# SCH_New-Project_2025-04-22.net
KiCad netlist of a schematic drawn in EasyEDA
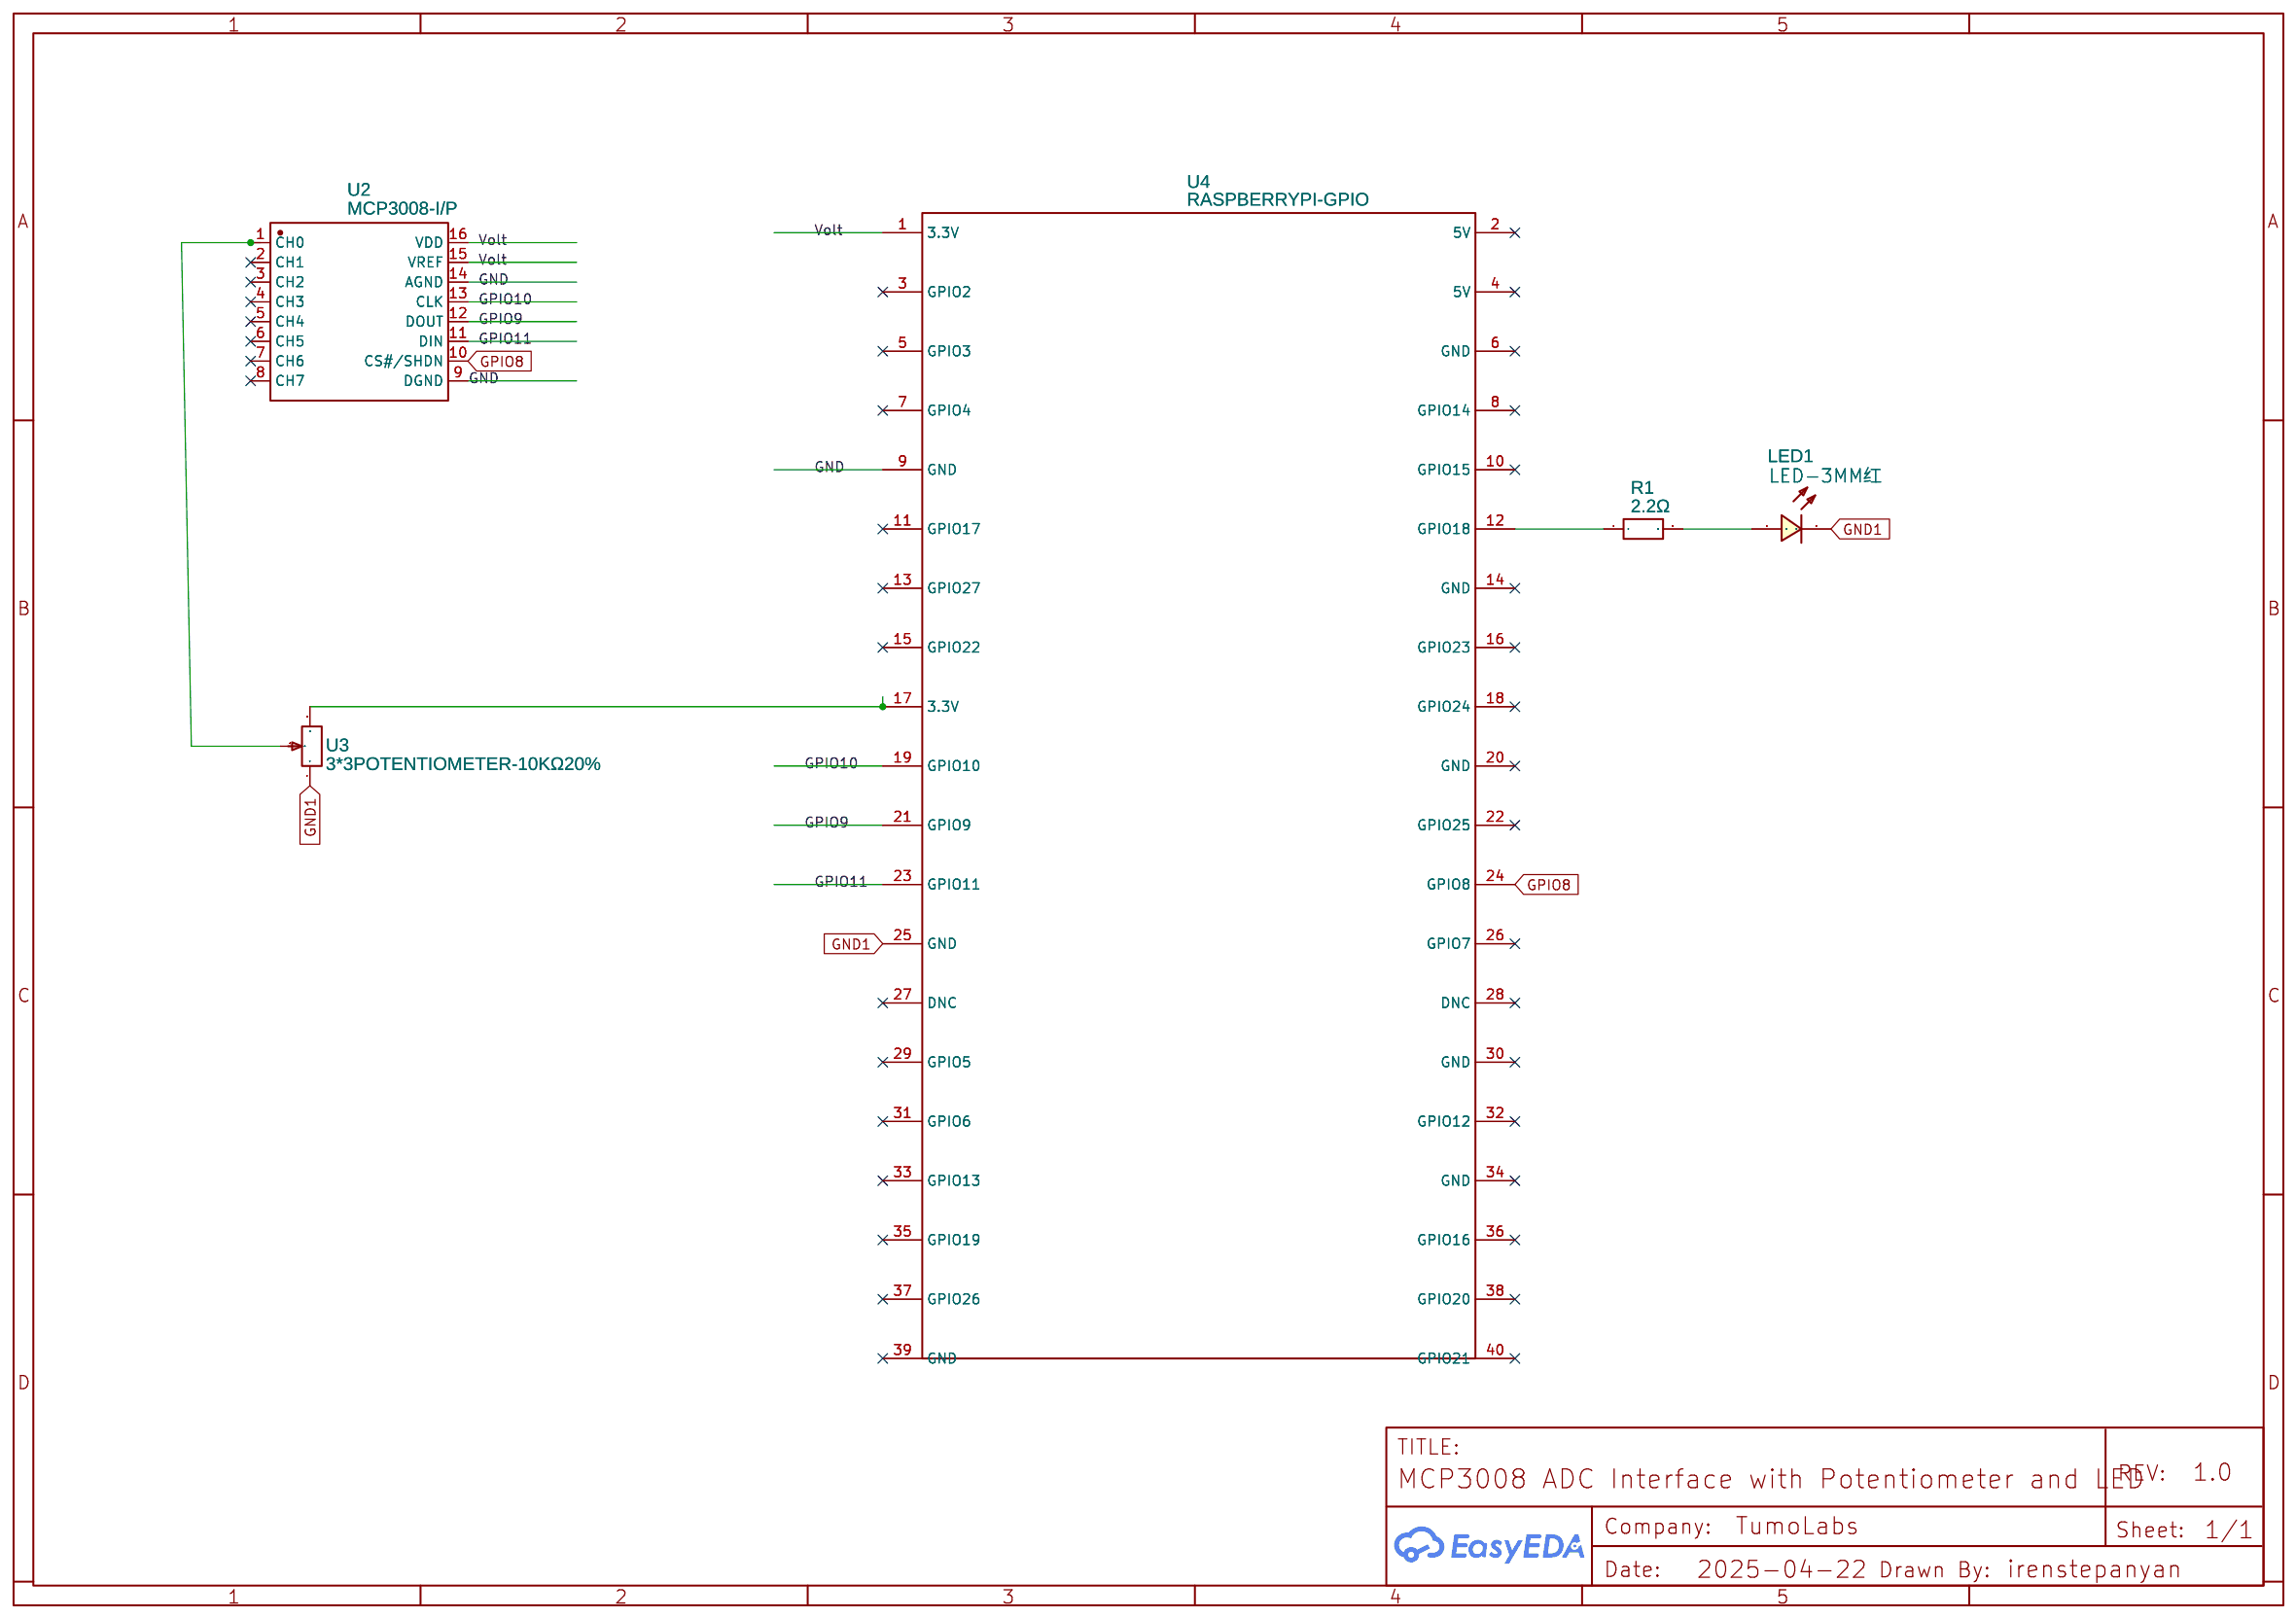
[diagram p0: schematic sheet]

(export (version "E")
  (design (tool "Eeschema 10.0.6"))
  (components
    (comp (ref "LED1")
      (value "LED-3MM红")
      (fields (field (name "Manufacturer Part") "LED-3mm红"))
      (libsource (lib "") (part "LED-3MM红"))
    )
    (comp (ref "R1")
      (value "2.2Ω")
      (fields
        (field (name "Manufacturer Part") "CERAMIC RESISTOR 10W/ 2,2 OHM")
        (field (name "Manufacturer") "Visaton")
      )
      (libsource (lib "") (part "CERAMIC RESISTOR 10W/ 2,2 OHM"))
    )
    (comp (ref "U2")
      (value "MCP3008-I/P")
      (fields (field (name "Manufacturer") "MICROCHIP(美国微芯)"))
      (libsource (lib "") (part "MCP3008-I/P"))
    )
    (comp (ref "U3")
      (value "3*3POTENTIOMETER-10KΩ20%")
      (fields (field (name "Manufacturer Part") "3*3Potentiometer-10kΩ20%"))
      (libsource (lib "") (part "3*3POTENTIOMETER-10KΩ20%"))
    )
    (comp (ref "U4") (value "RASPBERRYPI-GPIO") (libsource (lib "") (part "RASPBERRYPI-GPIO")))
  )
  (nets
    (net (code "1") (name "/GND") (class "Default")
      (node (ref "U2") (pin "14") (pinfunction "AGND_14") (pintype "unspecified"))
      (node (ref "U2") (pin "9") (pinfunction "DGND_9") (pintype "unspecified"))
      (node (ref "U4") (pin "9") (pinfunction "GND_9") (pintype "unspecified"))
    )
    (net (code "2") (name "/GPIO9") (class "Default")
      (node (ref "U2") (pin "12") (pinfunction "DOUT_12") (pintype "unspecified"))
      (node (ref "U4") (pin "21") (pinfunction "GPIO9_21") (pintype "unspecified"))
    )
    (net (code "3") (name "/GPIO10") (class "Default")
      (node (ref "U2") (pin "13") (pinfunction "CLK_13") (pintype "unspecified"))
      (node (ref "U4") (pin "19") (pinfunction "GPIO10_19") (pintype "unspecified"))
    )
    (net (code "4") (name "/GPIO11") (class "Default")
      (node (ref "U2") (pin "11") (pinfunction "DIN_11") (pintype "unspecified"))
      (node (ref "U4") (pin "23") (pinfunction "GPIO11_23") (pintype "unspecified"))
    )
    (net (code "5") (name "/Volt") (class "Default")
      (node (ref "U2") (pin "15") (pinfunction "VREF_15") (pintype "unspecified"))
      (node (ref "U2") (pin "16") (pinfunction "VDD_16") (pintype "unspecified"))
      (node (ref "U4") (pin "1") (pinfunction "3.3V_1") (pintype "unspecified"))
    )
    (net (code "6") (name "GND1") (class "Default")
      (node (ref "LED1") (pin "2") (pinfunction "2_2") (pintype "unspecified"))
      (node (ref "U3") (pin "1") (pinfunction "1_1") (pintype "input"))
      (node (ref "U4") (pin "25") (pinfunction "GND_25") (pintype "unspecified"))
    )
    (net (code "7") (name "GPIO8") (class "Default")
      (node (ref "U2") (pin "10") (pinfunction "CS#/SHDN_10") (pintype "unspecified"))
      (node (ref "U4") (pin "24") (pinfunction "GPIO8_24") (pintype "unspecified"))
    )
    (net (code "8") (name "Net-(LED1-Pad1)") (class "Default")
      (node (ref "LED1") (pin "1") (pinfunction "1_1") (pintype "unspecified"))
      (node (ref "R1") (pin "2") (pinfunction "2_2") (pintype "unspecified"))
    )
    (net (code "9") (name "Net-(U2-CH0)") (class "Default")
      (node (ref "U2") (pin "1") (pinfunction "CH0_1") (pintype "unspecified"))
      (node (ref "U3") (pin "2") (pinfunction "2_2") (pintype "input"))
    )
    (net (code "10") (name "Net-(U3-Pad3)") (class "Default")
      (node (ref "U3") (pin "3") (pinfunction "3_3") (pintype "input"))
      (node (ref "U4") (pin "17") (pinfunction "3.3V_17") (pintype "unspecified"))
    )
    (net (code "11") (name "Net-(U4-GPIO18)") (class "Default")
      (node (ref "R1") (pin "1") (pinfunction "1_1") (pintype "unspecified"))
      (node (ref "U4") (pin "12") (pinfunction "GPIO18_12") (pintype "unspecified"))
    )
    (net (code "12") (name "unconnected-(U2-CH1-Pad2)") (class "Default")
      (node (ref "U2") (pin "2") (pinfunction "CH1_2") (pintype "unspecified+no_connect"))
    )
    (net (code "13") (name "unconnected-(U2-CH2-Pad3)") (class "Default")
      (node (ref "U2") (pin "3") (pinfunction "CH2_3") (pintype "unspecified+no_connect"))
    )
    (net (code "14") (name "unconnected-(U2-CH3-Pad4)") (class "Default")
      (node (ref "U2") (pin "4") (pinfunction "CH3_4") (pintype "unspecified+no_connect"))
    )
    (net (code "15") (name "unconnected-(U2-CH4-Pad5)") (class "Default")
      (node (ref "U2") (pin "5") (pinfunction "CH4_5") (pintype "unspecified+no_connect"))
    )
    (net (code "16") (name "unconnected-(U2-CH5-Pad6)") (class "Default")
      (node (ref "U2") (pin "6") (pinfunction "CH5_6") (pintype "unspecified+no_connect"))
    )
    (net (code "17") (name "unconnected-(U2-CH6-Pad7)") (class "Default")
      (node (ref "U2") (pin "7") (pinfunction "CH6_7") (pintype "unspecified+no_connect"))
    )
    (net (code "18") (name "unconnected-(U2-CH7-Pad8)") (class "Default")
      (node (ref "U2") (pin "8") (pinfunction "CH7_8") (pintype "unspecified+no_connect"))
    )
    (net (code "19") (name "unconnected-(U4-5V-Pad2)") (class "Default")
      (node (ref "U4") (pin "2") (pinfunction "5V_2") (pintype "unspecified+no_connect"))
    )
    (net (code "20") (name "unconnected-(U4-5V-Pad4)") (class "Default")
      (node (ref "U4") (pin "4") (pinfunction "5V_4") (pintype "unspecified+no_connect"))
    )
    (net (code "21") (name "unconnected-(U4-DNC-Pad27)") (class "Default")
      (node (ref "U4") (pin "27") (pinfunction "DNC_27") (pintype "unspecified+no_connect"))
    )
    (net (code "22") (name "unconnected-(U4-DNC-Pad28)") (class "Default")
      (node (ref "U4") (pin "28") (pinfunction "DNC_28") (pintype "unspecified+no_connect"))
    )
    (net (code "23") (name "unconnected-(U4-GND-Pad6)") (class "Default")
      (node (ref "U4") (pin "6") (pinfunction "GND_6") (pintype "unspecified+no_connect"))
    )
    (net (code "24") (name "unconnected-(U4-GND-Pad14)") (class "Default")
      (node (ref "U4") (pin "14") (pinfunction "GND_14") (pintype "unspecified+no_connect"))
    )
    (net (code "25") (name "unconnected-(U4-GND-Pad20)") (class "Default")
      (node (ref "U4") (pin "20") (pinfunction "GND_20") (pintype "unspecified+no_connect"))
    )
    (net (code "26") (name "unconnected-(U4-GND-Pad30)") (class "Default")
      (node (ref "U4") (pin "30") (pinfunction "GND_30") (pintype "unspecified+no_connect"))
    )
    (net (code "27") (name "unconnected-(U4-GND-Pad34)") (class "Default")
      (node (ref "U4") (pin "34") (pinfunction "GND_34") (pintype "unspecified+no_connect"))
    )
    (net (code "28") (name "unconnected-(U4-GND-Pad39)") (class "Default")
      (node (ref "U4") (pin "39") (pinfunction "GND_39") (pintype "unspecified+no_connect"))
    )
    (net (code "29") (name "unconnected-(U4-GPIO2-Pad3)") (class "Default")
      (node (ref "U4") (pin "3") (pinfunction "GPIO2_3") (pintype "unspecified+no_connect"))
    )
    (net (code "30") (name "unconnected-(U4-GPIO3-Pad5)") (class "Default")
      (node (ref "U4") (pin "5") (pinfunction "GPIO3_5") (pintype "unspecified+no_connect"))
    )
    (net (code "31") (name "unconnected-(U4-GPIO4-Pad7)") (class "Default")
      (node (ref "U4") (pin "7") (pinfunction "GPIO4_7") (pintype "unspecified+no_connect"))
    )
    (net (code "32") (name "unconnected-(U4-GPIO5-Pad29)") (class "Default")
      (node (ref "U4") (pin "29") (pinfunction "GPIO5_29") (pintype "unspecified+no_connect"))
    )
    (net (code "33") (name "unconnected-(U4-GPIO6-Pad31)") (class "Default")
      (node (ref "U4") (pin "31") (pinfunction "GPIO6_31") (pintype "unspecified+no_connect"))
    )
    (net (code "34") (name "unconnected-(U4-GPIO7-Pad26)") (class "Default")
      (node (ref "U4") (pin "26") (pinfunction "GPIO7_26") (pintype "unspecified+no_connect"))
    )
    (net (code "35") (name "unconnected-(U4-GPIO12-Pad32)") (class "Default")
      (node (ref "U4") (pin "32") (pinfunction "GPIO12_32") (pintype "unspecified+no_connect"))
    )
    (net (code "36") (name "unconnected-(U4-GPIO13-Pad33)") (class "Default")
      (node (ref "U4") (pin "33") (pinfunction "GPIO13_33") (pintype "unspecified+no_connect"))
    )
    (net (code "37") (name "unconnected-(U4-GPIO14-Pad8)") (class "Default")
      (node (ref "U4") (pin "8") (pinfunction "GPIO14_8") (pintype "unspecified+no_connect"))
    )
    (net (code "38") (name "unconnected-(U4-GPIO15-Pad10)") (class "Default")
      (node (ref "U4") (pin "10") (pinfunction "GPIO15_10") (pintype "unspecified+no_connect"))
    )
    (net (code "39") (name "unconnected-(U4-GPIO16-Pad36)") (class "Default")
      (node (ref "U4") (pin "36") (pinfunction "GPIO16_36") (pintype "unspecified+no_connect"))
    )
    (net (code "40") (name "unconnected-(U4-GPIO17-Pad11)") (class "Default")
      (node (ref "U4") (pin "11") (pinfunction "GPIO17_11") (pintype "unspecified+no_connect"))
    )
    (net (code "41") (name "unconnected-(U4-GPIO19-Pad35)") (class "Default")
      (node (ref "U4") (pin "35") (pinfunction "GPIO19_35") (pintype "unspecified+no_connect"))
    )
    (net (code "42") (name "unconnected-(U4-GPIO20-Pad38)") (class "Default")
      (node (ref "U4") (pin "38") (pinfunction "GPIO20_38") (pintype "unspecified+no_connect"))
    )
    (net (code "43") (name "unconnected-(U4-GPIO21-Pad40)") (class "Default")
      (node (ref "U4") (pin "40") (pinfunction "GPIO21_40") (pintype "unspecified+no_connect"))
    )
    (net (code "44") (name "unconnected-(U4-GPIO22-Pad15)") (class "Default")
      (node (ref "U4") (pin "15") (pinfunction "GPIO22_15") (pintype "unspecified+no_connect"))
    )
    (net (code "45") (name "unconnected-(U4-GPIO23-Pad16)") (class "Default")
      (node (ref "U4") (pin "16") (pinfunction "GPIO23_16") (pintype "unspecified+no_connect"))
    )
    (net (code "46") (name "unconnected-(U4-GPIO24-Pad18)") (class "Default")
      (node (ref "U4") (pin "18") (pinfunction "GPIO24_18") (pintype "unspecified+no_connect"))
    )
    (net (code "47") (name "unconnected-(U4-GPIO25-Pad22)") (class "Default")
      (node (ref "U4") (pin "22") (pinfunction "GPIO25_22") (pintype "unspecified+no_connect"))
    )
    (net (code "48") (name "unconnected-(U4-GPIO26-Pad37)") (class "Default")
      (node (ref "U4") (pin "37") (pinfunction "GPIO26_37") (pintype "unspecified+no_connect"))
    )
    (net (code "49") (name "unconnected-(U4-GPIO27-Pad13)") (class "Default")
      (node (ref "U4") (pin "13") (pinfunction "GPIO27_13") (pintype "unspecified+no_connect"))
    )
  )
)
